# LCDuino.net
KiCad netlist of a schematic drawn in Altium Designer
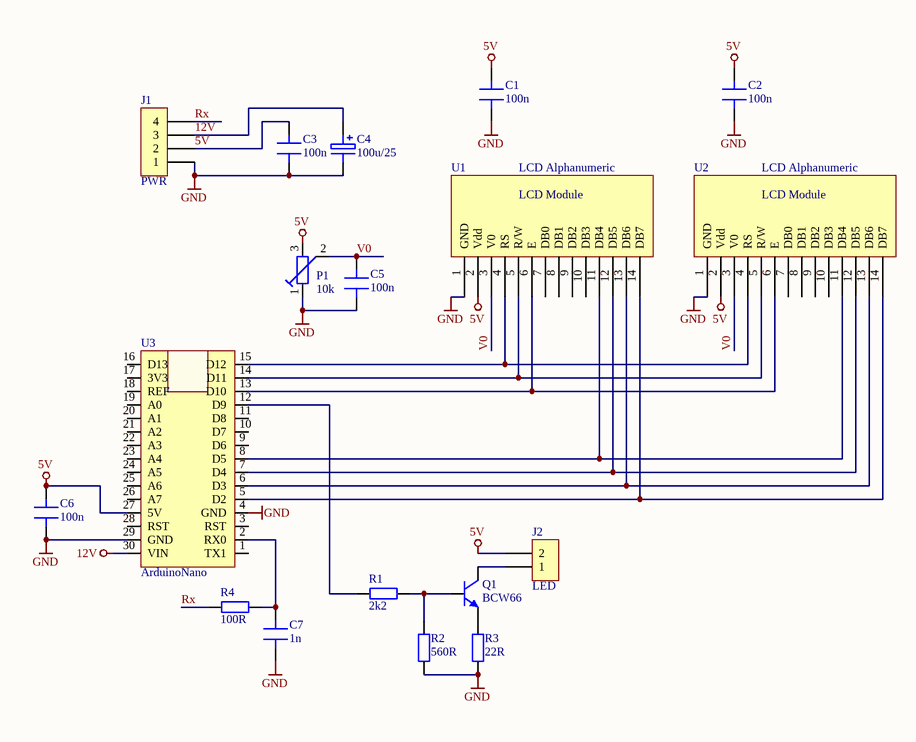
[diagram p0: LCDuino.SchDoc]

(export (version "E")
  (design (tool "Eeschema 10.0.6"))
  (components
    (comp (ref "C1")
      (value "100n")
      (footprint "0805")
      (description "kondenzator")
      (libsource (lib "jat") (part "C"))
    )
    (comp (ref "C2")
      (value "100n")
      (footprint "0805")
      (description "kondenzator")
      (libsource (lib "jat") (part "C"))
    )
    (comp (ref "C3")
      (value "100n")
      (footprint "0805")
      (description "kondenzator")
      (libsource (lib "jat") (part "C"))
    )
    (comp (ref "C4")
      (value "100u/25")
      (footprint "SMD D")
      (description "Kondenzator elektroliticky")
      (libsource (lib "jat") (part "C_EL"))
    )
    (comp (ref "C5")
      (value "100n")
      (footprint "0805")
      (description "kondenzator")
      (libsource (lib "jat") (part "C"))
    )
    (comp (ref "C6")
      (value "100n")
      (footprint "0805")
      (description "kondenzator")
      (libsource (lib "jat") (part "C"))
    )
    (comp (ref "C7")
      (value "1n")
      (footprint "0805")
      (description "kondenzator")
      (libsource (lib "jat") (part "C"))
    )
    (comp (ref "J1")
      (value "PWR")
      (footprint "MTS04008")
      (description "Connector")
      (libsource (lib "jat") (part "CON4"))
    )
    (comp (ref "J2")
      (value "LED")
      (footprint "2pin100")
      (description "Connector")
      (libsource (lib "jat") (part "CON2"))
    )
    (comp (ref "P1") (value "10k") (footprint "CA6VSMD") (libsource (lib "jat") (part "TRIMER")))
    (comp (ref "Q1")
      (value "BCW66")
      (footprint "jat:SOT23")
      (description "NPN SMD")
      (libsource (lib "jat") (part "BC846"))
    )
    (comp (ref "R1")
      (value "2k2")
      (footprint "0805")
      (description "Rezistor")
      (libsource (lib "jat") (part "R"))
    )
    (comp (ref "R2")
      (value "560R")
      (footprint "0805")
      (description "Rezistor")
      (libsource (lib "jat") (part "R"))
    )
    (comp (ref "R3")
      (value "22R")
      (footprint "0805")
      (description "Rezistor")
      (libsource (lib "jat") (part "R"))
    )
    (comp (ref "R4")
      (value "100R")
      (footprint "0805")
      (description "Rezistor")
      (libsource (lib "jat") (part "R"))
    )
    (comp (ref "U1")
      (value "LCD Alphanumeric")
      (footprint "LCDM14pin")
      (description "OLED")
      (libsource (lib "jat") (part "LCD_Modul"))
    )
    (comp (ref "U2")
      (value "LCD Alphanumeric")
      (footprint "LCDM_2x7pin")
      (description "OLED")
      (libsource (lib "jat") (part "LCD_Modul"))
    )
    (comp (ref "U3")
      (value "ArduinoNano")
      (footprint "ArduinoNano")
      (description "Arduino Nano V3.0 ATmega328 16M 5V CH340G")
      (libsource (lib "jat") (part "ArduinoNano"))
    )
  )
  (nets
    (net (code "1") (name "/Rx") (class "Default")
      (node (ref "J1") (pin "4") (pinfunction "4_4") (pintype "passive"))
      (node (ref "R4") (pin "1") (pinfunction "1_1") (pintype "passive"))
    )
    (net (code "2") (name "/V0") (class "Default")
      (node (ref "C5") (pin "1") (pinfunction "1_1") (pintype "passive"))
      (node (ref "P1") (pin "2") (pinfunction "2_2") (pintype "passive"))
      (node (ref "U1") (pin "3") (pinfunction "V0_3") (pintype "passive"))
      (node (ref "U2") (pin "3") (pinfunction "V0_3") (pintype "passive"))
    )
    (net (code "3") (name "5V") (class "Default")
      (node (ref "C1") (pin "1") (pinfunction "1_1") (pintype "passive"))
      (node (ref "C2") (pin "1") (pinfunction "1_1") (pintype "passive"))
      (node (ref "C3") (pin "1") (pinfunction "1_1") (pintype "passive"))
      (node (ref "C6") (pin "1") (pinfunction "1_1") (pintype "passive"))
      (node (ref "J1") (pin "2") (pinfunction "2_2") (pintype "passive"))
      (node (ref "J2") (pin "2") (pinfunction "2_2") (pintype "passive"))
      (node (ref "P1") (pin "3") (pinfunction "3_3") (pintype "passive"))
      (node (ref "U1") (pin "2") (pinfunction "Vdd_2") (pintype "passive"))
      (node (ref "U2") (pin "2") (pinfunction "Vdd_2") (pintype "passive"))
      (node (ref "U3") (pin "27") (pinfunction "5V_27") (pintype "passive"))
    )
    (net (code "4") (name "12V") (class "Default")
      (node (ref "C4") (pin "1") (pinfunction "1_1") (pintype "passive"))
      (node (ref "J1") (pin "3") (pinfunction "3_3") (pintype "passive"))
      (node (ref "U3") (pin "30") (pinfunction "VIN_30") (pintype "passive"))
    )
    (net (code "5") (name "GND") (class "Default")
      (node (ref "C1") (pin "2") (pinfunction "2_2") (pintype "passive"))
      (node (ref "C2") (pin "2") (pinfunction "2_2") (pintype "passive"))
      (node (ref "C3") (pin "2") (pinfunction "2_2") (pintype "passive"))
      (node (ref "C4") (pin "2") (pinfunction "2_2") (pintype "passive"))
      (node (ref "C5") (pin "2") (pinfunction "2_2") (pintype "passive"))
      (node (ref "C6") (pin "2") (pinfunction "2_2") (pintype "passive"))
      (node (ref "C7") (pin "2") (pinfunction "2_2") (pintype "passive"))
      (node (ref "J1") (pin "1") (pinfunction "1_1") (pintype "passive"))
      (node (ref "P1") (pin "1") (pinfunction "1_1") (pintype "passive"))
      (node (ref "R2") (pin "1") (pinfunction "1_1") (pintype "passive"))
      (node (ref "R3") (pin "1") (pinfunction "1_1") (pintype "passive"))
      (node (ref "U1") (pin "1") (pinfunction "GND_1") (pintype "passive"))
      (node (ref "U2") (pin "1") (pinfunction "GND_1") (pintype "passive"))
      (node (ref "U3") (pin "29") (pinfunction "GND_29") (pintype "passive"))
      (node (ref "U3") (pin "4") (pinfunction "GND_4") (pintype "passive"))
    )
    (net (code "6") (name "Net-(Q1-B)") (class "Default")
      (node (ref "Q1") (pin "1") (pinfunction "B_1") (pintype "passive"))
      (node (ref "R1") (pin "2") (pinfunction "2_2") (pintype "passive"))
      (node (ref "R2") (pin "2") (pinfunction "2_2") (pintype "passive"))
    )
    (net (code "7") (name "Net-(Q1-C)") (class "Default")
      (node (ref "J2") (pin "1") (pinfunction "1_1") (pintype "passive"))
      (node (ref "Q1") (pin "3") (pinfunction "C_3") (pintype "passive"))
    )
    (net (code "8") (name "Net-(Q1-E)") (class "Default")
      (node (ref "Q1") (pin "2") (pinfunction "E_2") (pintype "passive"))
      (node (ref "R3") (pin "2") (pinfunction "2_2") (pintype "passive"))
    )
    (net (code "9") (name "Net-(U1-DB4)") (class "Default")
      (node (ref "U1") (pin "11") (pinfunction "DB4_11") (pintype "passive"))
      (node (ref "U2") (pin "11") (pinfunction "DB4_11") (pintype "passive"))
      (node (ref "U3") (pin "8") (pinfunction "D5_8") (pintype "passive"))
    )
    (net (code "10") (name "Net-(U1-DB5)") (class "Default")
      (node (ref "U1") (pin "12") (pinfunction "DB5_12") (pintype "passive"))
      (node (ref "U2") (pin "12") (pinfunction "DB5_12") (pintype "passive"))
      (node (ref "U3") (pin "7") (pinfunction "D4_7") (pintype "passive"))
    )
    (net (code "11") (name "Net-(U1-DB6)") (class "Default")
      (node (ref "U1") (pin "13") (pinfunction "DB6_13") (pintype "passive"))
      (node (ref "U2") (pin "13") (pinfunction "DB6_13") (pintype "passive"))
      (node (ref "U3") (pin "6") (pinfunction "D3_6") (pintype "passive"))
    )
    (net (code "12") (name "Net-(U1-DB7)") (class "Default")
      (node (ref "U1") (pin "14") (pinfunction "DB7_14") (pintype "passive"))
      (node (ref "U2") (pin "14") (pinfunction "DB7_14") (pintype "passive"))
      (node (ref "U3") (pin "5") (pinfunction "D2_5") (pintype "passive"))
    )
    (net (code "13") (name "Net-(U1-E)") (class "Default")
      (node (ref "U1") (pin "6") (pinfunction "E_6") (pintype "passive"))
      (node (ref "U2") (pin "6") (pinfunction "E_6") (pintype "passive"))
      (node (ref "U3") (pin "13") (pinfunction "D10_13") (pintype "passive"))
    )
    (net (code "14") (name "Net-(U1-RS)") (class "Default")
      (node (ref "U1") (pin "4") (pinfunction "RS_4") (pintype "passive"))
      (node (ref "U2") (pin "4") (pinfunction "RS_4") (pintype "passive"))
      (node (ref "U3") (pin "15") (pinfunction "D12_15") (pintype "passive"))
    )
    (net (code "15") (name "Net-(U1-R{slash}W)") (class "Default")
      (node (ref "U1") (pin "5") (pinfunction "R/W_5") (pintype "passive"))
      (node (ref "U2") (pin "5") (pinfunction "R/W_5") (pintype "passive"))
      (node (ref "U3") (pin "14") (pinfunction "D11_14") (pintype "passive"))
    )
    (net (code "16") (name "Net-(U3-D9)") (class "Default")
      (node (ref "R1") (pin "1") (pinfunction "1_1") (pintype "passive"))
      (node (ref "U3") (pin "12") (pinfunction "D9_12") (pintype "passive"))
    )
    (net (code "17") (name "Net-(U3-RX0)") (class "Default")
      (node (ref "C7") (pin "1") (pinfunction "1_1") (pintype "passive"))
      (node (ref "R4") (pin "2") (pinfunction "2_2") (pintype "passive"))
      (node (ref "U3") (pin "2") (pinfunction "RX0_2") (pintype "passive"))
    )
    (net (code "18") (name "unconnected-(U1-DB0-Pad7)") (class "Default")
      (node (ref "U1") (pin "7") (pinfunction "DB0_7") (pintype "passive"))
    )
    (net (code "19") (name "unconnected-(U1-DB1-Pad8)") (class "Default")
      (node (ref "U1") (pin "8") (pinfunction "DB1_8") (pintype "passive"))
    )
    (net (code "20") (name "unconnected-(U1-DB2-Pad9)") (class "Default")
      (node (ref "U1") (pin "9") (pinfunction "DB2_9") (pintype "passive"))
    )
    (net (code "21") (name "unconnected-(U1-DB3-Pad10)") (class "Default")
      (node (ref "U1") (pin "10") (pinfunction "DB3_10") (pintype "passive"))
    )
    (net (code "22") (name "unconnected-(U2-DB0-Pad7)") (class "Default")
      (node (ref "U2") (pin "7") (pinfunction "DB0_7") (pintype "passive"))
    )
    (net (code "23") (name "unconnected-(U2-DB1-Pad8)") (class "Default")
      (node (ref "U2") (pin "8") (pinfunction "DB1_8") (pintype "passive"))
    )
    (net (code "24") (name "unconnected-(U2-DB2-Pad9)") (class "Default")
      (node (ref "U2") (pin "9") (pinfunction "DB2_9") (pintype "passive"))
    )
    (net (code "25") (name "unconnected-(U2-DB3-Pad10)") (class "Default")
      (node (ref "U2") (pin "10") (pinfunction "DB3_10") (pintype "passive"))
    )
    (net (code "26") (name "unconnected-(U3-3V3-Pad17)") (class "Default")
      (node (ref "U3") (pin "17") (pinfunction "3V3_17") (pintype "passive"))
    )
    (net (code "27") (name "unconnected-(U3-A0-Pad19)") (class "Default")
      (node (ref "U3") (pin "19") (pinfunction "A0_19") (pintype "passive"))
    )
    (net (code "28") (name "unconnected-(U3-A1-Pad20)") (class "Default")
      (node (ref "U3") (pin "20") (pinfunction "A1_20") (pintype "passive"))
    )
    (net (code "29") (name "unconnected-(U3-A2-Pad21)") (class "Default")
      (node (ref "U3") (pin "21") (pinfunction "A2_21") (pintype "passive"))
    )
    (net (code "30") (name "unconnected-(U3-A3-Pad22)") (class "Default")
      (node (ref "U3") (pin "22") (pinfunction "A3_22") (pintype "passive"))
    )
    (net (code "31") (name "unconnected-(U3-A4-Pad23)") (class "Default")
      (node (ref "U3") (pin "23") (pinfunction "A4_23") (pintype "passive"))
    )
    (net (code "32") (name "unconnected-(U3-A5-Pad24)") (class "Default")
      (node (ref "U3") (pin "24") (pinfunction "A5_24") (pintype "passive"))
    )
    (net (code "33") (name "unconnected-(U3-A6-Pad25)") (class "Default")
      (node (ref "U3") (pin "25") (pinfunction "A6_25") (pintype "passive"))
    )
    (net (code "34") (name "unconnected-(U3-A7-Pad26)") (class "Default")
      (node (ref "U3") (pin "26") (pinfunction "A7_26") (pintype "passive"))
    )
    (net (code "35") (name "unconnected-(U3-D6-Pad9)") (class "Default")
      (node (ref "U3") (pin "9") (pinfunction "D6_9") (pintype "passive"))
    )
    (net (code "36") (name "unconnected-(U3-D7-Pad10)") (class "Default")
      (node (ref "U3") (pin "10") (pinfunction "D7_10") (pintype "passive"))
    )
    (net (code "37") (name "unconnected-(U3-D8-Pad11)") (class "Default")
      (node (ref "U3") (pin "11") (pinfunction "D8_11") (pintype "passive"))
    )
    (net (code "38") (name "unconnected-(U3-D13-Pad16)") (class "Default")
      (node (ref "U3") (pin "16") (pinfunction "D13_16") (pintype "passive"))
    )
    (net (code "39") (name "unconnected-(U3-REF-Pad18)") (class "Default")
      (node (ref "U3") (pin "18") (pinfunction "REF_18") (pintype "passive"))
    )
    (net (code "40") (name "unconnected-(U3-RST-Pad3)") (class "Default")
      (node (ref "U3") (pin "3") (pinfunction "RST_3") (pintype "passive"))
    )
    (net (code "41") (name "unconnected-(U3-RST-Pad28)") (class "Default")
      (node (ref "U3") (pin "28") (pinfunction "RST_28") (pintype "passive"))
    )
    (net (code "42") (name "unconnected-(U3-TX1-Pad1)") (class "Default")
      (node (ref "U3") (pin "1") (pinfunction "TX1_1") (pintype "passive"))
    )
  )
)
